# CH382SSP.net
KiCad netlist of a schematic drawn in Altium Designer
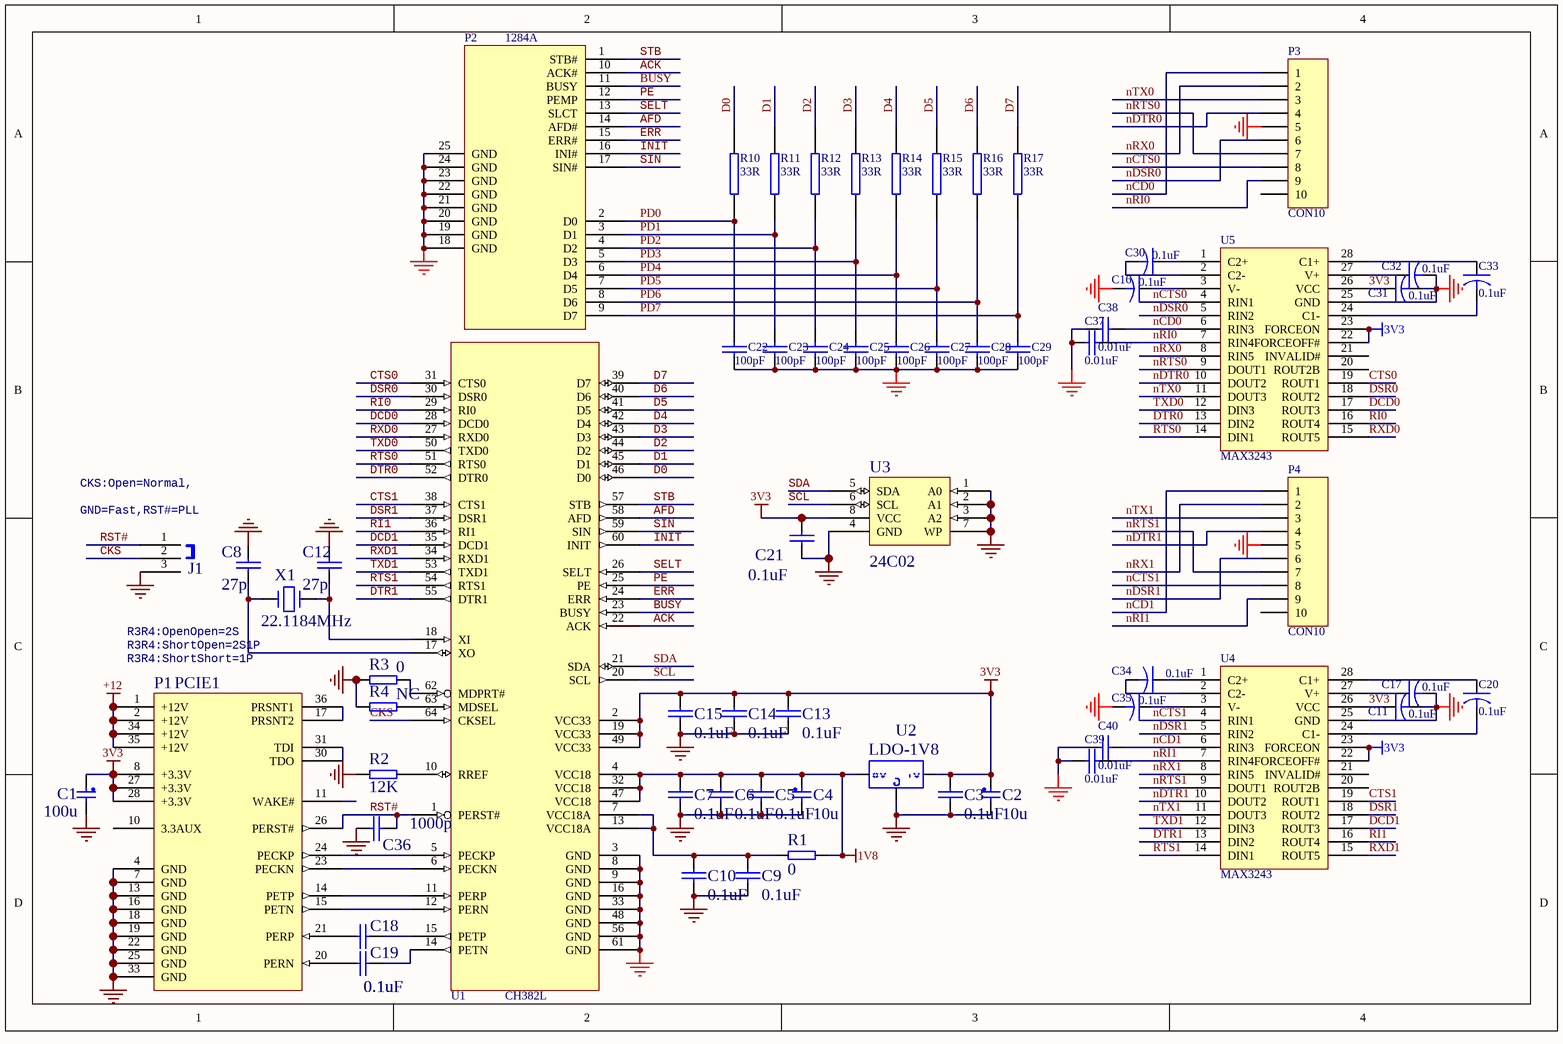
[diagram p0: CH382SSP.SchDoc]

(export (version "E")
  (design (tool "Eeschema 10.0.6"))
  (components
    (comp (ref "C1") (value "100u") (footprint "CD0.1") (libsource (lib "*") (part "Pro89C.tmp_100u_10")))
    (comp (ref "C2") (value "10u") (footprint "3216") (libsource (lib "*") (part "Pro89C.tmp_10u_4")))
    (comp (ref "C3") (value "0.1uF") (footprint "0603") (libsource (lib "*") (part "Pro89C.tmp_0.1u_3")))
    (comp (ref "C4") (value "10u") (footprint "3216") (libsource (lib "*") (part "Pro89C.tmp_10u_4")))
    (comp (ref "C5") (value "0.1uF") (footprint "0603") (libsource (lib "*") (part "Pro89C.tmp_0.1u_3")))
    (comp (ref "C6") (value "0.1uF") (footprint "0603") (libsource (lib "*") (part "Pro89C.tmp_0.1u_3")))
    (comp (ref "C7") (value "0.1uF") (footprint "0603") (libsource (lib "*") (part "Pro89C.tmp_0.1u_3")))
    (comp (ref "C8") (value "27p") (footprint "0603") (libsource (lib "*") (part "Pro5B1.tmp_27p_3")))
    (comp (ref "C9") (value "0.1uF") (footprint "0603") (libsource (lib "*") (part "Pro89C.tmp_0.1u_3")))
    (comp (ref "C10") (value "0.1uF") (footprint "0603") (libsource (lib "*") (part "Pro89C.tmp_0.1u_3")))
    (comp (ref "C11")
      (value "0.1uF")
      (footprint "0603")
      (description "Capacitor")
      (libsource (lib "*") (part "CAPACITOR"))
    )
    (comp (ref "C12") (value "27p") (footprint "0603") (libsource (lib "*") (part "Pro5B1.tmp_27p_3")))
    (comp (ref "C13") (value "0.1uF") (footprint "0603") (libsource (lib "*") (part "Pro89C.tmp_0.1u_3")))
    (comp (ref "C14") (value "0.1uF") (footprint "0603") (libsource (lib "*") (part "Pro89C.tmp_0.1u_3")))
    (comp (ref "C15") (value "0.1uF") (footprint "0603") (libsource (lib "*") (part "Pro89C.tmp_0.1u_3")))
    (comp (ref "C16")
      (value "0.1uF")
      (footprint "0603")
      (description "Capacitor")
      (libsource (lib "*") (part "CAPACITOR"))
    )
    (comp (ref "C17")
      (value "0.1uF")
      (footprint "0603")
      (description "Capacitor")
      (libsource (lib "*") (part "CAPACITOR"))
    )
    (comp (ref "C18") (value "0.1uF") (footprint "0603") (libsource (lib "*") (part "Pro89C.tmp_0.1u_70")))
    (comp (ref "C19") (value "0.1uF") (footprint "0603") (libsource (lib "*") (part "Pro89C.tmp_0.1u_71")))
    (comp (ref "C20")
      (value "0.1uF")
      (footprint "0603")
      (description "Capacitor")
      (libsource (lib "*") (part "CAPACITOR"))
    )
    (comp (ref "C21") (value "0.1uF") (footprint "0603") (libsource (lib "*") (part "Pro89C.tmp_0.1u_3")))
    (comp (ref "C22")
      (value "100pF")
      (footprint "0603")
      (description "Capacitor")
      (libsource (lib "*") (part "CAP"))
    )
    (comp (ref "C23")
      (value "100pF")
      (footprint "0603")
      (description "Capacitor")
      (libsource (lib "*") (part "CAP"))
    )
    (comp (ref "C24")
      (value "100pF")
      (footprint "0603")
      (description "Capacitor")
      (libsource (lib "*") (part "CAP"))
    )
    (comp (ref "C25")
      (value "100pF")
      (footprint "0603")
      (description "Capacitor")
      (libsource (lib "*") (part "CAP"))
    )
    (comp (ref "C26")
      (value "100pF")
      (footprint "0603")
      (description "Capacitor")
      (libsource (lib "*") (part "CAP"))
    )
    (comp (ref "C27")
      (value "100pF")
      (footprint "0603")
      (description "Capacitor")
      (libsource (lib "*") (part "CAP"))
    )
    (comp (ref "C28")
      (value "100pF")
      (footprint "0603")
      (description "Capacitor")
      (libsource (lib "*") (part "CAP"))
    )
    (comp (ref "C29")
      (value "100pF")
      (footprint "0603")
      (description "Capacitor")
      (libsource (lib "*") (part "CAP"))
    )
    (comp (ref "C30")
      (value "0.1uF")
      (footprint "0603")
      (description "Capacitor")
      (libsource (lib "*") (part "CAPACITOR"))
    )
    (comp (ref "C31")
      (value "0.1uF")
      (footprint "0603")
      (description "Capacitor")
      (libsource (lib "*") (part "CAPACITOR"))
    )
    (comp (ref "C32")
      (value "0.1uF")
      (footprint "0603")
      (description "Capacitor")
      (libsource (lib "*") (part "CAPACITOR"))
    )
    (comp (ref "C33")
      (value "0.1uF")
      (footprint "0603")
      (description "Capacitor")
      (libsource (lib "*") (part "CAPACITOR"))
    )
    (comp (ref "C34")
      (value "0.1uF")
      (footprint "0603")
      (description "Capacitor")
      (libsource (lib "*") (part "CAPACITOR"))
    )
    (comp (ref "C35")
      (value "0.1uF")
      (footprint "0603")
      (description "Capacitor")
      (libsource (lib "*") (part "CAPACITOR"))
    )
    (comp (ref "C36") (value "1000p") (footprint "0603") (libsource (lib "*") (part "Pro5B1.tmp_27p_3")))
    (comp (ref "C37")
      (value "0.01uF")
      (footprint "0603")
      (description "Capacitor")
      (libsource (lib "*") (part "CAP"))
    )
    (comp (ref "C38")
      (value "0.01uF")
      (footprint "0603")
      (description "Capacitor")
      (libsource (lib "*") (part "CAP"))
    )
    (comp (ref "C39")
      (value "0.01uF")
      (footprint "0603")
      (description "Capacitor")
      (libsource (lib "*") (part "CAP"))
    )
    (comp (ref "C40")
      (value "0.01uF")
      (footprint "0603")
      (description "Capacitor")
      (libsource (lib "*") (part "CAP"))
    )
    (comp (ref "J1") (value "3JUMPS") (footprint "SIP3") (libsource (lib "*") (part "Pro5B1.tmp_3JUMPS_1")))
    (comp (ref "P1") (value "PCIE1") (footprint "PCIE1") (libsource (lib "*") (part "Pro89C.tmp_PCIE1_69")))
    (comp (ref "P2") (value "1284A") (footprint "DB25RA/F") (libsource (lib "*") (part "1284A")))
    (comp (ref "P3")
      (value "CON10")
      (footprint "IDC10")
      (description "Connector")
      (libsource (lib "*") (part "CON10"))
    )
    (comp (ref "P4")
      (value "CON10")
      (footprint "IDC10")
      (description "Connector")
      (libsource (lib "*") (part "CON10"))
    )
    (comp (ref "R1") (value "0") (footprint "0805") (libsource (lib "*") (part "Pro89C.tmp_0_1")))
    (comp (ref "R2") (value "12K") (footprint "0603") (libsource (lib "*") (part "Pro5B1.tmp_12K_15")))
    (comp (ref "R3") (value "0") (footprint "0603") (libsource (lib "*") (part "Pro3F8.tmp_0_4")))
    (comp (ref "R4") (value "NC") (footprint "0603") (libsource (lib "*") (part "Pro3F8.tmp_0_4")))
    (comp (ref "R10") (value "33R") (footprint "0603") (libsource (lib "*") (part "RES2")))
    (comp (ref "R11") (value "33R") (footprint "0603") (libsource (lib "*") (part "RES2")))
    (comp (ref "R12") (value "33R") (footprint "0603") (libsource (lib "*") (part "RES2")))
    (comp (ref "R13") (value "33R") (footprint "0603") (libsource (lib "*") (part "RES2")))
    (comp (ref "R14") (value "33R") (footprint "0603") (libsource (lib "*") (part "RES2")))
    (comp (ref "R15") (value "33R") (footprint "0603") (libsource (lib "*") (part "RES2")))
    (comp (ref "R16") (value "33R") (footprint "0603") (libsource (lib "*") (part "RES2")))
    (comp (ref "R17") (value "33R") (footprint "0603") (libsource (lib "*") (part "RES2")))
    (comp (ref "U1")
      (value "CH382L")
      (footprint "LQFP64")
      (description "PCIe to 2S1P: Print Port / Parallel and Dual 16C550 UART with 256 byte FIFO")
      (libsource (lib "*") (part "CH382L"))
    )
    (comp (ref "U2")
      (value "LDO-1V8")
      (footprint "SOT-223")
      (libsource (lib "*") (part "Pro89C.tmp_LDO-1V8_68"))
    )
    (comp (ref "U3") (value "24C02") (footprint "SOP8") (libsource (lib "*") (part "Pro89C.tmp_24C02_11")))
    (comp (ref "U4") (value "MAX3243") (footprint "SSOP28") (libsource (lib "*") (part "MAX3243")))
    (comp (ref "U5") (value "MAX3243") (footprint "SSOP28") (libsource (lib "*") (part "MAX3243")))
    (comp (ref "X1")
      (value "22.1184MHz")
      (footprint "XTAL62/28")
      (libsource (lib "*") (part "Pro5B1.tmp_22.1184MHz_4"))
    )
  )
  (nets
    (net (code "1") (name "+12") (class "Default")
      (node (ref "P1") (pin "1") (pinfunction "+12V_1") (pintype "power_in"))
      (node (ref "P1") (pin "2") (pinfunction "+12V_2") (pintype "power_in"))
      (node (ref "P1") (pin "34") (pinfunction "+12V_34") (pintype "power_in"))
      (node (ref "P1") (pin "35") (pinfunction "+12V_35") (pintype "power_in"))
    )
    (net (code "2") (name "/ACK") (class "Default")
      (node (ref "P2") (pin "10") (pinfunction "ACK#_10") (pintype "passive"))
      (node (ref "U1") (pin "22") (pinfunction "ACK_22") (pintype "input"))
    )
    (net (code "3") (name "/AFD") (class "Default")
      (node (ref "P2") (pin "14") (pinfunction "AFD#_14") (pintype "passive"))
      (node (ref "U1") (pin "58") (pinfunction "AFD_58") (pintype "output"))
    )
    (net (code "4") (name "/BUSY") (class "Default")
      (node (ref "P2") (pin "11") (pinfunction "BUSY_11") (pintype "passive"))
      (node (ref "U1") (pin "23") (pinfunction "BUSY_23") (pintype "input"))
    )
    (net (code "5") (name "/CKS") (class "Default")
      (node (ref "J1") (pin "2") (pintype "passive"))
      (node (ref "U1") (pin "64") (pinfunction "CKSEL_64") (pintype "input"))
    )
    (net (code "6") (name "/CTS0") (class "Default")
      (node (ref "U1") (pin "31") (pinfunction "CTS0_31") (pintype "input"))
      (node (ref "U5") (pin "19") (pinfunction "ROUT1_19") (pintype "passive"))
    )
    (net (code "7") (name "/CTS1") (class "Default")
      (node (ref "U1") (pin "38") (pinfunction "CTS1_38") (pintype "input"))
      (node (ref "U4") (pin "19") (pinfunction "ROUT1_19") (pintype "passive"))
    )
    (net (code "8") (name "/D0") (class "Default")
      (node (ref "R10") (pin "2") (pinfunction "2_2") (pintype "passive"))
      (node (ref "U1") (pin "46") (pinfunction "D0_46") (pintype "bidirectional"))
    )
    (net (code "9") (name "/D1") (class "Default")
      (node (ref "R11") (pin "2") (pinfunction "2_2") (pintype "passive"))
      (node (ref "U1") (pin "45") (pinfunction "D1_45") (pintype "bidirectional"))
    )
    (net (code "10") (name "/D2") (class "Default")
      (node (ref "R12") (pin "2") (pinfunction "2_2") (pintype "passive"))
      (node (ref "U1") (pin "44") (pinfunction "D2_44") (pintype "bidirectional"))
    )
    (net (code "11") (name "/D3") (class "Default")
      (node (ref "R13") (pin "2") (pinfunction "2_2") (pintype "passive"))
      (node (ref "U1") (pin "43") (pinfunction "D3_43") (pintype "bidirectional"))
    )
    (net (code "12") (name "/D4") (class "Default")
      (node (ref "R14") (pin "2") (pinfunction "2_2") (pintype "passive"))
      (node (ref "U1") (pin "42") (pinfunction "D4_42") (pintype "bidirectional"))
    )
    (net (code "13") (name "/D5") (class "Default")
      (node (ref "R15") (pin "2") (pinfunction "2_2") (pintype "passive"))
      (node (ref "U1") (pin "41") (pinfunction "D5_41") (pintype "bidirectional"))
    )
    (net (code "14") (name "/D6") (class "Default")
      (node (ref "R16") (pin "2") (pinfunction "2_2") (pintype "passive"))
      (node (ref "U1") (pin "40") (pinfunction "D6_40") (pintype "bidirectional"))
    )
    (net (code "15") (name "/D7") (class "Default")
      (node (ref "R17") (pin "2") (pinfunction "2_2") (pintype "passive"))
      (node (ref "U1") (pin "39") (pinfunction "D7_39") (pintype "bidirectional"))
    )
    (net (code "16") (name "/DCD0") (class "Default")
      (node (ref "U1") (pin "28") (pinfunction "DCD0_28") (pintype "input"))
      (node (ref "U5") (pin "17") (pinfunction "ROUT3_17") (pintype "passive"))
    )
    (net (code "17") (name "/DCD1") (class "Default")
      (node (ref "U1") (pin "35") (pinfunction "DCD1_35") (pintype "input"))
      (node (ref "U4") (pin "17") (pinfunction "ROUT3_17") (pintype "passive"))
    )
    (net (code "18") (name "/DSR0") (class "Default")
      (node (ref "U1") (pin "30") (pinfunction "DSR0_30") (pintype "input"))
      (node (ref "U5") (pin "18") (pinfunction "ROUT2_18") (pintype "passive"))
    )
    (net (code "19") (name "/DSR1") (class "Default")
      (node (ref "U1") (pin "37") (pinfunction "DSR1_37") (pintype "input"))
      (node (ref "U4") (pin "18") (pinfunction "ROUT2_18") (pintype "passive"))
    )
    (net (code "20") (name "/DTR0") (class "Default")
      (node (ref "U1") (pin "52") (pinfunction "DTR0_52") (pintype "output"))
      (node (ref "U5") (pin "13") (pinfunction "DIN2_13") (pintype "passive"))
    )
    (net (code "21") (name "/DTR1") (class "Default")
      (node (ref "U1") (pin "55") (pinfunction "DTR1_55") (pintype "output"))
      (node (ref "U4") (pin "13") (pinfunction "DIN2_13") (pintype "passive"))
    )
    (net (code "22") (name "/ERR") (class "Default")
      (node (ref "P2") (pin "15") (pinfunction "ERR#_15") (pintype "passive"))
      (node (ref "U1") (pin "24") (pinfunction "ERR_24") (pintype "input"))
    )
    (net (code "23") (name "/INIT") (class "Default")
      (node (ref "P2") (pin "16") (pinfunction "INI#_16") (pintype "passive"))
      (node (ref "U1") (pin "60") (pinfunction "INIT_60") (pintype "output"))
    )
    (net (code "24") (name "/PD0") (class "Default")
      (node (ref "C22") (pin "1") (pinfunction "1_1") (pintype "passive"))
      (node (ref "P2") (pin "2") (pinfunction "D0_2") (pintype "passive"))
      (node (ref "R10") (pin "1") (pinfunction "1_1") (pintype "passive"))
    )
    (net (code "25") (name "/PD1") (class "Default")
      (node (ref "C23") (pin "1") (pinfunction "1_1") (pintype "passive"))
      (node (ref "P2") (pin "3") (pinfunction "D1_3") (pintype "passive"))
      (node (ref "R11") (pin "1") (pinfunction "1_1") (pintype "passive"))
    )
    (net (code "26") (name "/PD2") (class "Default")
      (node (ref "C24") (pin "1") (pinfunction "1_1") (pintype "passive"))
      (node (ref "P2") (pin "4") (pinfunction "D2_4") (pintype "passive"))
      (node (ref "R12") (pin "1") (pinfunction "1_1") (pintype "passive"))
    )
    (net (code "27") (name "/PD3") (class "Default")
      (node (ref "C25") (pin "1") (pinfunction "1_1") (pintype "passive"))
      (node (ref "P2") (pin "5") (pinfunction "D3_5") (pintype "passive"))
      (node (ref "R13") (pin "1") (pinfunction "1_1") (pintype "passive"))
    )
    (net (code "28") (name "/PD4") (class "Default")
      (node (ref "C26") (pin "1") (pinfunction "1_1") (pintype "passive"))
      (node (ref "P2") (pin "6") (pinfunction "D4_6") (pintype "passive"))
      (node (ref "R14") (pin "1") (pinfunction "1_1") (pintype "passive"))
    )
    (net (code "29") (name "/PD5") (class "Default")
      (node (ref "C27") (pin "1") (pinfunction "1_1") (pintype "passive"))
      (node (ref "P2") (pin "7") (pinfunction "D5_7") (pintype "passive"))
      (node (ref "R15") (pin "1") (pinfunction "1_1") (pintype "passive"))
    )
    (net (code "30") (name "/PD6") (class "Default")
      (node (ref "C28") (pin "1") (pinfunction "1_1") (pintype "passive"))
      (node (ref "P2") (pin "8") (pinfunction "D6_8") (pintype "passive"))
      (node (ref "R16") (pin "1") (pinfunction "1_1") (pintype "passive"))
    )
    (net (code "31") (name "/PD7") (class "Default")
      (node (ref "C29") (pin "1") (pinfunction "1_1") (pintype "passive"))
      (node (ref "P2") (pin "9") (pinfunction "D7_9") (pintype "passive"))
      (node (ref "R17") (pin "1") (pinfunction "1_1") (pintype "passive"))
    )
    (net (code "32") (name "/PE") (class "Default")
      (node (ref "P2") (pin "12") (pinfunction "PEMP_12") (pintype "passive"))
      (node (ref "U1") (pin "25") (pinfunction "PE_25") (pintype "input"))
    )
    (net (code "33") (name "/RI0") (class "Default")
      (node (ref "U1") (pin "29") (pinfunction "RI0_29") (pintype "input"))
      (node (ref "U5") (pin "16") (pinfunction "ROUT4_16") (pintype "passive"))
    )
    (net (code "34") (name "/RI1") (class "Default")
      (node (ref "U1") (pin "36") (pinfunction "RI1_36") (pintype "input"))
      (node (ref "U4") (pin "16") (pinfunction "ROUT4_16") (pintype "passive"))
    )
    (net (code "35") (name "/RST#") (class "Default")
      (node (ref "C36") (pin "1") (pintype "passive"))
      (node (ref "J1") (pin "1") (pintype "passive"))
      (node (ref "P1") (pin "26") (pinfunction "PERST#_26") (pintype "output"))
      (node (ref "U1") (pin "1") (pinfunction "PERST#_1") (pintype "input"))
    )
    (net (code "36") (name "/RTS0") (class "Default")
      (node (ref "U1") (pin "51") (pinfunction "RTS0_51") (pintype "output"))
      (node (ref "U5") (pin "14") (pinfunction "DIN1_14") (pintype "passive"))
    )
    (net (code "37") (name "/RTS1") (class "Default")
      (node (ref "U1") (pin "54") (pinfunction "RTS1_54") (pintype "output"))
      (node (ref "U4") (pin "14") (pinfunction "DIN1_14") (pintype "passive"))
    )
    (net (code "38") (name "/RXD0") (class "Default")
      (node (ref "U1") (pin "27") (pinfunction "RXD0_27") (pintype "input"))
      (node (ref "U5") (pin "15") (pinfunction "ROUT5_15") (pintype "passive"))
    )
    (net (code "39") (name "/RXD1") (class "Default")
      (node (ref "U1") (pin "34") (pinfunction "RXD1_34") (pintype "input"))
      (node (ref "U4") (pin "15") (pinfunction "ROUT5_15") (pintype "passive"))
    )
    (net (code "40") (name "/SCL") (class "Default")
      (node (ref "U1") (pin "20") (pinfunction "SCL_20") (pintype "output"))
      (node (ref "U3") (pin "6") (pinfunction "SCL_6") (pintype "bidirectional"))
    )
    (net (code "41") (name "/SDA") (class "Default")
      (node (ref "U1") (pin "21") (pinfunction "SDA_21") (pintype "bidirectional"))
      (node (ref "U3") (pin "5") (pinfunction "SDA_5") (pintype "bidirectional"))
    )
    (net (code "42") (name "/SELT") (class "Default")
      (node (ref "P2") (pin "13") (pinfunction "SLCT_13") (pintype "passive"))
      (node (ref "U1") (pin "26") (pinfunction "SELT_26") (pintype "input"))
    )
    (net (code "43") (name "/SIN") (class "Default")
      (node (ref "P2") (pin "17") (pinfunction "SIN#_17") (pintype "passive"))
      (node (ref "U1") (pin "59") (pinfunction "SIN_59") (pintype "output"))
    )
    (net (code "44") (name "/STB") (class "Default")
      (node (ref "P2") (pin "1") (pinfunction "STB#_1") (pintype "passive"))
      (node (ref "U1") (pin "57") (pinfunction "STB_57") (pintype "output"))
    )
    (net (code "45") (name "/TXD0") (class "Default")
      (node (ref "U1") (pin "50") (pinfunction "TXD0_50") (pintype "output"))
      (node (ref "U5") (pin "12") (pinfunction "DIN3_12") (pintype "passive"))
    )
    (net (code "46") (name "/TXD1") (class "Default")
      (node (ref "U1") (pin "53") (pinfunction "TXD1_53") (pintype "output"))
      (node (ref "U4") (pin "12") (pinfunction "DIN3_12") (pintype "passive"))
    )
    (net (code "47") (name "/nCD0") (class "Default")
      (node (ref "C38") (pin "2") (pinfunction "2_2") (pintype "passive"))
      (node (ref "P3") (pin "1") (pinfunction "1_1") (pintype "passive"))
      (node (ref "U5") (pin "6") (pinfunction "RIN3_6") (pintype "passive"))
    )
    (net (code "48") (name "/nCD1") (class "Default")
      (node (ref "C40") (pin "2") (pinfunction "2_2") (pintype "passive"))
      (node (ref "P4") (pin "1") (pinfunction "1_1") (pintype "passive"))
      (node (ref "U4") (pin "6") (pinfunction "RIN3_6") (pintype "passive"))
    )
    (net (code "49") (name "/nCTS0") (class "Default")
      (node (ref "P3") (pin "8") (pinfunction "8_8") (pintype "passive"))
      (node (ref "U5") (pin "4") (pinfunction "RIN1_4") (pintype "passive"))
    )
    (net (code "50") (name "/nCTS1") (class "Default")
      (node (ref "P4") (pin "8") (pinfunction "8_8") (pintype "passive"))
      (node (ref "U4") (pin "4") (pinfunction "RIN1_4") (pintype "passive"))
    )
    (net (code "51") (name "/nDSR0") (class "Default")
      (node (ref "P3") (pin "6") (pinfunction "6_6") (pintype "passive"))
      (node (ref "U5") (pin "5") (pinfunction "RIN2_5") (pintype "passive"))
    )
    (net (code "52") (name "/nDSR1") (class "Default")
      (node (ref "P4") (pin "6") (pinfunction "6_6") (pintype "passive"))
      (node (ref "U4") (pin "5") (pinfunction "RIN2_5") (pintype "passive"))
    )
    (net (code "53") (name "/nDTR0") (class "Default")
      (node (ref "P3") (pin "4") (pinfunction "4_4") (pintype "passive"))
      (node (ref "U5") (pin "10") (pinfunction "DOUT2_10") (pintype "passive"))
    )
    (net (code "54") (name "/nDTR1") (class "Default")
      (node (ref "P4") (pin "4") (pinfunction "4_4") (pintype "passive"))
      (node (ref "U4") (pin "10") (pinfunction "DOUT2_10") (pintype "passive"))
    )
    (net (code "55") (name "/nRI0") (class "Default")
      (node (ref "C37") (pin "2") (pinfunction "2_2") (pintype "passive"))
      (node (ref "P3") (pin "9") (pinfunction "9_9") (pintype "passive"))
      (node (ref "U5") (pin "7") (pinfunction "RIN4_7") (pintype "passive"))
    )
    (net (code "56") (name "/nRI1") (class "Default")
      (node (ref "C39") (pin "2") (pinfunction "2_2") (pintype "passive"))
      (node (ref "P4") (pin "9") (pinfunction "9_9") (pintype "passive"))
      (node (ref "U4") (pin "7") (pinfunction "RIN4_7") (pintype "passive"))
    )
    (net (code "57") (name "/nRTS0") (class "Default")
      (node (ref "P3") (pin "7") (pinfunction "7_7") (pintype "passive"))
      (node (ref "U5") (pin "9") (pinfunction "DOUT1_9") (pintype "passive"))
    )
    (net (code "58") (name "/nRTS1") (class "Default")
      (node (ref "P4") (pin "7") (pinfunction "7_7") (pintype "passive"))
      (node (ref "U4") (pin "9") (pinfunction "DOUT1_9") (pintype "passive"))
    )
    (net (code "59") (name "/nRX0") (class "Default")
      (node (ref "P3") (pin "2") (pinfunction "2_2") (pintype "passive"))
      (node (ref "U5") (pin "8") (pinfunction "RIN5_8") (pintype "passive"))
    )
    (net (code "60") (name "/nRX1") (class "Default")
      (node (ref "P4") (pin "2") (pinfunction "2_2") (pintype "passive"))
      (node (ref "U4") (pin "8") (pinfunction "RIN5_8") (pintype "passive"))
    )
    (net (code "61") (name "/nTX0") (class "Default")
      (node (ref "P3") (pin "3") (pinfunction "3_3") (pintype "passive"))
      (node (ref "U5") (pin "11") (pinfunction "DOUT3_11") (pintype "passive"))
    )
    (net (code "62") (name "/nTX1") (class "Default")
      (node (ref "P4") (pin "3") (pinfunction "3_3") (pintype "passive"))
      (node (ref "U4") (pin "11") (pinfunction "DOUT3_11") (pintype "passive"))
    )
    (net (code "63") (name "1V8") (class "Default")
      (node (ref "C4") (pin "1") (pintype "passive"))
      (node (ref "C5") (pin "1") (pintype "passive"))
      (node (ref "C6") (pin "1") (pintype "passive"))
      (node (ref "C7") (pin "1") (pintype "passive"))
      (node (ref "R1") (pin "1") (pintype "passive"))
      (node (ref "U1") (pin "32") (pinfunction "VCC18_32") (pintype "power_in"))
      (node (ref "U1") (pin "4") (pinfunction "VCC18_4") (pintype "power_in"))
      (node (ref "U1") (pin "47") (pinfunction "VCC18_47") (pintype "power_in"))
      (node (ref "U2") (pin "2") (pintype "passive"))
    )
    (net (code "64") (name "3V3") (class "Default")
      (node (ref "C1") (pin "1") (pintype "passive"))
      (node (ref "C11") (pin "1") (pinfunction "1_1") (pintype "passive"))
      (node (ref "C13") (pin "1") (pintype "passive"))
      (node (ref "C14") (pin "1") (pintype "passive"))
      (node (ref "C15") (pin "1") (pintype "passive"))
      (node (ref "C2") (pin "1") (pintype "passive"))
      (node (ref "C21") (pin "1") (pintype "passive"))
      (node (ref "C3") (pin "1") (pintype "passive"))
      (node (ref "C31") (pin "1") (pinfunction "1_1") (pintype "passive"))
      (node (ref "P1") (pin "27") (pinfunction "+3.3V_27") (pintype "power_in"))
      (node (ref "P1") (pin "28") (pinfunction "+3.3V_28") (pintype "power_in"))
      (node (ref "P1") (pin "8") (pinfunction "+3.3V_8") (pintype "power_in"))
      (node (ref "U1") (pin "19") (pinfunction "VCC33_19") (pintype "power_in"))
      (node (ref "U1") (pin "2") (pinfunction "VCC33_2") (pintype "power_in"))
      (node (ref "U1") (pin "49") (pinfunction "VCC33_49") (pintype "power_in"))
      (node (ref "U2") (pin "3") (pintype "passive"))
      (node (ref "U3") (pin "8") (pinfunction "VCC_8") (pintype "power_in"))
      (node (ref "U4") (pin "22") (pinfunction "FORCEOFF#_22") (pintype "passive"))
      (node (ref "U4") (pin "23") (pinfunction "FORCEON_23") (pintype "passive"))
      (node (ref "U4") (pin "26") (pinfunction "VCC_26") (pintype "passive"))
      (node (ref "U5") (pin "22") (pinfunction "FORCEOFF#_22") (pintype "passive"))
      (node (ref "U5") (pin "23") (pinfunction "FORCEON_23") (pintype "passive"))
      (node (ref "U5") (pin "26") (pinfunction "VCC_26") (pintype "passive"))
    )
    (net (code "65") (name "GND") (class "Default")
      (node (ref "C1") (pin "2") (pintype "passive"))
      (node (ref "C10") (pin "2") (pintype "passive"))
      (node (ref "C11") (pin "2") (pinfunction "2_2") (pintype "passive"))
      (node (ref "C12") (pin "2") (pintype "passive"))
      (node (ref "C13") (pin "2") (pintype "passive"))
      (node (ref "C14") (pin "2") (pintype "passive"))
      (node (ref "C15") (pin "2") (pintype "passive"))
      (node (ref "C16") (pin "2") (pinfunction "2_2") (pintype "passive"))
      (node (ref "C17") (pin "2") (pinfunction "2_2") (pintype "passive"))
      (node (ref "C2") (pin "2") (pintype "passive"))
      (node (ref "C21") (pin "2") (pintype "passive"))
      (node (ref "C22") (pin "2") (pinfunction "2_2") (pintype "passive"))
      (node (ref "C23") (pin "2") (pinfunction "2_2") (pintype "passive"))
      (node (ref "C24") (pin "2") (pinfunction "2_2") (pintype "passive"))
      (node (ref "C25") (pin "2") (pinfunction "2_2") (pintype "passive"))
      (node (ref "C26") (pin "2") (pinfunction "2_2") (pintype "passive"))
      (node (ref "C27") (pin "2") (pinfunction "2_2") (pintype "passive"))
      (node (ref "C28") (pin "2") (pinfunction "2_2") (pintype "passive"))
      (node (ref "C29") (pin "2") (pinfunction "2_2") (pintype "passive"))
      (node (ref "C3") (pin "2") (pintype "passive"))
      (node (ref "C31") (pin "2") (pinfunction "2_2") (pintype "passive"))
      (node (ref "C32") (pin "2") (pinfunction "2_2") (pintype "passive"))
      (node (ref "C35") (pin "2") (pinfunction "2_2") (pintype "passive"))
      (node (ref "C36") (pin "2") (pintype "passive"))
      (node (ref "C37") (pin "1") (pinfunction "1_1") (pintype "passive"))
      (node (ref "C38") (pin "1") (pinfunction "1_1") (pintype "passive"))
      (node (ref "C39") (pin "1") (pinfunction "1_1") (pintype "passive"))
      (node (ref "C4") (pin "2") (pintype "passive"))
      (node (ref "C40") (pin "1") (pinfunction "1_1") (pintype "passive"))
      (node (ref "C5") (pin "2") (pintype "passive"))
      (node (ref "C6") (pin "2") (pintype "passive"))
      (node (ref "C7") (pin "2") (pintype "passive"))
      (node (ref "C8") (pin "2") (pintype "passive"))
      (node (ref "C9") (pin "2") (pintype "passive"))
      (node (ref "J1") (pin "3") (pintype "passive"))
      (node (ref "P1") (pin "13") (pinfunction "GND_13") (pintype "power_in"))
      (node (ref "P1") (pin "16") (pinfunction "GND_16") (pintype "power_in"))
      (node (ref "P1") (pin "18") (pinfunction "GND_18") (pintype "power_in"))
      (node (ref "P1") (pin "19") (pinfunction "GND_19") (pintype "power_in"))
      (node (ref "P1") (pin "22") (pinfunction "GND_22") (pintype "power_in"))
      (node (ref "P1") (pin "25") (pinfunction "GND_25") (pintype "power_in"))
      (node (ref "P1") (pin "33") (pinfunction "GND_33") (pintype "power_in"))
      (node (ref "P1") (pin "4") (pinfunction "GND_4") (pintype "power_in"))
      (node (ref "P1") (pin "7") (pinfunction "GND_7") (pintype "power_in"))
      (node (ref "P2") (pin "18") (pinfunction "GND_18") (pintype "passive"))
      (node (ref "P2") (pin "19") (pinfunction "GND_19") (pintype "passive"))
      (node (ref "P2") (pin "20") (pinfunction "GND_20") (pintype "passive"))
      (node (ref "P2") (pin "21") (pinfunction "GND_21") (pintype "passive"))
      (node (ref "P2") (pin "22") (pinfunction "GND_22") (pintype "passive"))
      (node (ref "P2") (pin "23") (pinfunction "GND_23") (pintype "passive"))
      (node (ref "P2") (pin "24") (pinfunction "GND_24") (pintype "passive"))
      (node (ref "P2") (pin "25") (pinfunction "GND_25") (pintype "passive"))
      (node (ref "P3") (pin "5") (pinfunction "5_5") (pintype "passive"))
      (node (ref "P4") (pin "5") (pinfunction "5_5") (pintype "passive"))
      (node (ref "R2") (pin "1") (pintype "passive"))
      (node (ref "R3") (pin "2") (pintype "passive"))
      (node (ref "R4") (pin "2") (pintype "passive"))
      (node (ref "U1") (pin "16") (pinfunction "GND_16") (pintype "power_in"))
      (node (ref "U1") (pin "3") (pinfunction "GND_3") (pintype "power_in"))
      (node (ref "U1") (pin "33") (pinfunction "GND_33") (pintype "power_in"))
      (node (ref "U1") (pin "48") (pinfunction "GND_48") (pintype "power_in"))
      (node (ref "U1") (pin "56") (pinfunction "GND_56") (pintype "power_in"))
      (node (ref "U1") (pin "61") (pinfunction "GND_61") (pintype "power_in"))
      (node (ref "U1") (pin "8") (pinfunction "GND_8") (pintype "power_in"))
      (node (ref "U1") (pin "9") (pinfunction "GND_9") (pintype "power_in"))
      (node (ref "U2") (pin "1") (pintype "passive"))
      (node (ref "U3") (pin "1") (pinfunction "A0_1") (pintype "input"))
      (node (ref "U3") (pin "2") (pinfunction "A1_2") (pintype "input"))
      (node (ref "U3") (pin "3") (pinfunction "A2_3") (pintype "input"))
      (node (ref "U3") (pin "4") (pinfunction "GND_4") (pintype "power_in"))
      (node (ref "U3") (pin "7") (pinfunction "WP_7") (pintype "passive"))
      (node (ref "U4") (pin "25") (pinfunction "GND_25") (pintype "passive"))
      (node (ref "U5") (pin "25") (pinfunction "GND_25") (pintype "passive"))
    )
    (net (code "66") (name "Net-(C10-Pad1)") (class "Default")
      (node (ref "C10") (pin "1") (pintype "passive"))
      (node (ref "C9") (pin "1") (pintype "passive"))
      (node (ref "R1") (pin "2") (pintype "passive"))
      (node (ref "U1") (pin "13") (pinfunction "VCC18A_13") (pintype "power_in"))
      (node (ref "U1") (pin "7") (pinfunction "VCC18A_7") (pintype "power_in"))
    )
    (net (code "67") (name "Net-(P1-PECKN)") (class "Default")
      (node (ref "P1") (pin "23") (pinfunction "PECKN_23") (pintype "output"))
      (node (ref "U1") (pin "6") (pinfunction "PECKN_6") (pintype "input"))
    )
    (net (code "68") (name "Net-(P1-PECKP)") (class "Default")
      (node (ref "P1") (pin "24") (pinfunction "PECKP_24") (pintype "output"))
      (node (ref "U1") (pin "5") (pinfunction "PECKP_5") (pintype "input"))
    )
    (net (code "69") (name "Net-(P1-PERN)") (class "Default")
      (node (ref "C19") (pin "1") (pintype "passive"))
      (node (ref "P1") (pin "20") (pinfunction "PERN_20") (pintype "input"))
    )
    (net (code "70") (name "Net-(P1-PERP)") (class "Default")
      (node (ref "C18") (pin "1") (pintype "passive"))
      (node (ref "P1") (pin "21") (pinfunction "PERP_21") (pintype "input"))
    )
    (net (code "71") (name "Net-(P1-PETN)") (class "Default")
      (node (ref "P1") (pin "15") (pinfunction "PETN_15") (pintype "output"))
      (node (ref "U1") (pin "12") (pinfunction "PERN_12") (pintype "input"))
    )
    (net (code "72") (name "Net-(P1-PETP)") (class "Default")
      (node (ref "P1") (pin "14") (pinfunction "PETP_14") (pintype "output"))
      (node (ref "U1") (pin "11") (pinfunction "PERP_11") (pintype "input"))
    )
    (net (code "73") (name "Net-(P1-PRSNT1)") (class "Default")
      (node (ref "P1") (pin "17") (pinfunction "PRSNT2_17") (pintype "passive"))
      (node (ref "P1") (pin "36") (pinfunction "PRSNT1_36") (pintype "passive"))
    )
    (net (code "74") (name "Net-(P1-TDI)") (class "Default")
      (node (ref "P1") (pin "30") (pinfunction "TDO_30") (pintype "passive"))
      (node (ref "P1") (pin "31") (pinfunction "TDI_31") (pintype "passive"))
    )
    (net (code "75") (name "Net-(U1-MDPRT#)") (class "Default")
      (node (ref "R3") (pin "1") (pintype "passive"))
      (node (ref "U1") (pin "62") (pinfunction "MDPRT#_62") (pintype "input"))
    )
    (net (code "76") (name "Net-(U1-MDSEL)") (class "Default")
      (node (ref "R4") (pin "1") (pintype "passive"))
      (node (ref "U1") (pin "63") (pinfunction "MDSEL_63") (pintype "input"))
    )
    (net (code "77") (name "Net-(U1-PETN)") (class "Default")
      (node (ref "C19") (pin "2") (pintype "passive"))
      (node (ref "U1") (pin "14") (pinfunction "PETN_14") (pintype "output"))
    )
    (net (code "78") (name "Net-(U1-PETP)") (class "Default")
      (node (ref "C18") (pin "2") (pintype "passive"))
      (node (ref "U1") (pin "15") (pinfunction "PETP_15") (pintype "output"))
    )
    (net (code "79") (name "Net-(U1-RREF)") (class "Default")
      (node (ref "R2") (pin "2") (pintype "passive"))
      (node (ref "U1") (pin "10") (pinfunction "RREF_10") (pintype "bidirectional"))
    )
    (net (code "80") (name "Net-(U1-XI)") (class "Default")
      (node (ref "C12") (pin "1") (pintype "passive"))
      (node (ref "U1") (pin "18") (pinfunction "XI_18") (pintype "input"))
      (node (ref "X1") (pin "1") (pintype "passive"))
    )
    (net (code "81") (name "Net-(U1-XO)") (class "Default")
      (node (ref "C8") (pin "1") (pintype "passive"))
      (node (ref "U1") (pin "17") (pinfunction "XO_17") (pintype "bidirectional"))
      (node (ref "X1") (pin "2") (pintype "passive"))
    )
    (net (code "82") (name "Net-(U4-C1+)") (class "Default")
      (node (ref "C20") (pin "1") (pinfunction "1_1") (pintype "passive"))
      (node (ref "U4") (pin "28") (pinfunction "C1+_28") (pintype "passive"))
    )
    (net (code "83") (name "Net-(U4-C1-)") (class "Default")
      (node (ref "C20") (pin "2") (pinfunction "2_2") (pintype "passive"))
      (node (ref "U4") (pin "24") (pinfunction "C1-_24") (pintype "passive"))
    )
    (net (code "84") (name "Net-(U4-C2+)") (class "Default")
      (node (ref "C34") (pin "1") (pinfunction "1_1") (pintype "passive"))
      (node (ref "U4") (pin "1") (pinfunction "C2+_1") (pintype "passive"))
    )
    (net (code "85") (name "Net-(U4-C2-)") (class "Default")
      (node (ref "C34") (pin "2") (pinfunction "2_2") (pintype "passive"))
      (node (ref "U4") (pin "2") (pinfunction "C2-_2") (pintype "passive"))
    )
    (net (code "86") (name "Net-(U4-V+)") (class "Default")
      (node (ref "C17") (pin "1") (pinfunction "1_1") (pintype "passive"))
      (node (ref "U4") (pin "27") (pinfunction "V+_27") (pintype "passive"))
    )
    (net (code "87") (name "Net-(U4-V-)") (class "Default")
      (node (ref "C35") (pin "1") (pinfunction "1_1") (pintype "passive"))
      (node (ref "U4") (pin "3") (pinfunction "V-_3") (pintype "passive"))
    )
    (net (code "88") (name "Net-(U5-C1+)") (class "Default")
      (node (ref "C33") (pin "1") (pinfunction "1_1") (pintype "passive"))
      (node (ref "U5") (pin "28") (pinfunction "C1+_28") (pintype "passive"))
    )
    (net (code "89") (name "Net-(U5-C1-)") (class "Default")
      (node (ref "C33") (pin "2") (pinfunction "2_2") (pintype "passive"))
      (node (ref "U5") (pin "24") (pinfunction "C1-_24") (pintype "passive"))
    )
    (net (code "90") (name "Net-(U5-C2+)") (class "Default")
      (node (ref "C30") (pin "1") (pinfunction "1_1") (pintype "passive"))
      (node (ref "U5") (pin "1") (pinfunction "C2+_1") (pintype "passive"))
    )
    (net (code "91") (name "Net-(U5-C2-)") (class "Default")
      (node (ref "C30") (pin "2") (pinfunction "2_2") (pintype "passive"))
      (node (ref "U5") (pin "2") (pinfunction "C2-_2") (pintype "passive"))
    )
    (net (code "92") (name "Net-(U5-V+)") (class "Default")
      (node (ref "C32") (pin "1") (pinfunction "1_1") (pintype "passive"))
      (node (ref "U5") (pin "27") (pinfunction "V+_27") (pintype "passive"))
    )
    (net (code "93") (name "Net-(U5-V-)") (class "Default")
      (node (ref "C16") (pin "1") (pinfunction "1_1") (pintype "passive"))
      (node (ref "U5") (pin "3") (pinfunction "V-_3") (pintype "passive"))
    )
    (net (code "94") (name "unconnected-(P1-3.3AUX-Pad10)") (class "Default")
      (node (ref "P1") (pin "10") (pinfunction "3.3AUX_10") (pintype "power_in"))
    )
    (net (code "95") (name "unconnected-(P1-WAKE#-Pad11)") (class "Default")
      (node (ref "P1") (pin "11") (pinfunction "WAKE#_11") (pintype "passive"))
    )
    (net (code "96") (name "unconnected-(P3-Pad10)") (class "Default")
      (node (ref "P3") (pin "10") (pinfunction "10_10") (pintype "passive"))
    )
    (net (code "97") (name "unconnected-(P4-Pad10)") (class "Default")
      (node (ref "P4") (pin "10") (pinfunction "10_10") (pintype "passive"))
    )
    (net (code "98") (name "unconnected-(U4-INVALID#-Pad21)") (class "Default")
      (node (ref "U4") (pin "21") (pinfunction "INVALID#_21") (pintype "passive"))
    )
    (net (code "99") (name "unconnected-(U4-ROUT2B-Pad20)") (class "Default")
      (node (ref "U4") (pin "20") (pinfunction "ROUT2B_20") (pintype "passive"))
    )
    (net (code "100") (name "unconnected-(U5-INVALID#-Pad21)") (class "Default")
      (node (ref "U5") (pin "21") (pinfunction "INVALID#_21") (pintype "passive"))
    )
    (net (code "101") (name "unconnected-(U5-ROUT2B-Pad20)") (class "Default")
      (node (ref "U5") (pin "20") (pinfunction "ROUT2B_20") (pintype "passive"))
    )
  )
)
